# ethernet_camera.net
KiCad netlist of a schematic drawn in EAGLE
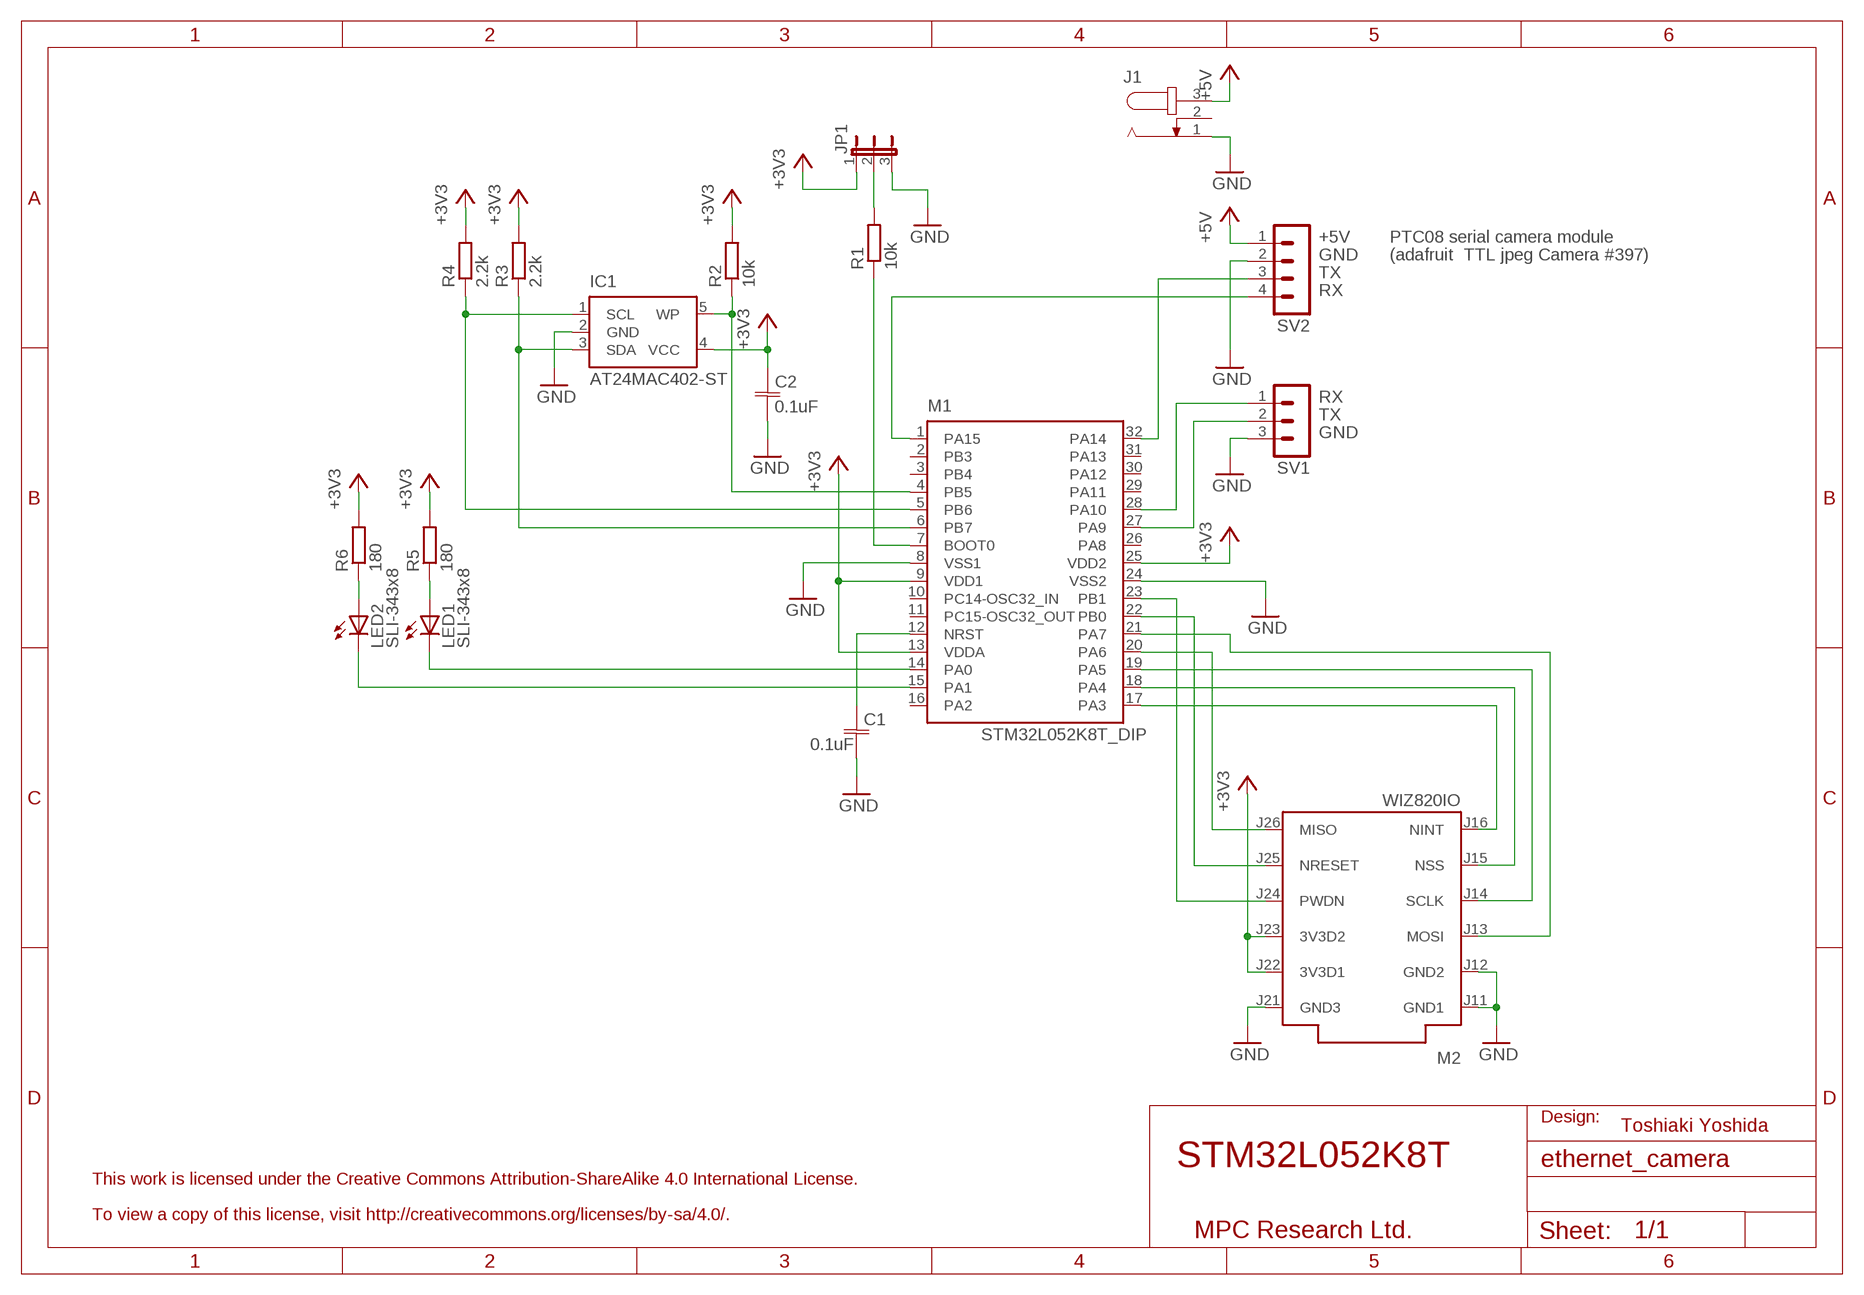
[diagram p0: schematic, sheet 1]

(export (version "E")
  (design (tool "Eeschema 10.0.6"))
  (components
    (comp (ref "C1")
      (value "0.1uF")
      (footprint "eagle-import:C050-024X044")
      (libsource (lib "eagle-import") (part "C-JIS050-024X044"))
    )
    (comp (ref "C2")
      (value "0.1uF")
      (footprint "eagle-import:C050-024X044")
      (libsource (lib "eagle-import") (part "C-JIS050-024X044"))
    )
    (comp (ref "IC1")
      (value "AT24MAC402-ST")
      (footprint "eagle-import:SOT23-5L")
      (libsource (lib "eagle-import") (part "AT24MAC402-ST"))
    )
    (comp (ref "J1")
      (value "JACK-PLUG0")
      (footprint "eagle-import:SPC4077")
      (libsource (lib "eagle-import") (part "JACK-PLUG0"))
    )
    (comp (ref "JP1")
      (value "JP2E")
      (footprint "eagle-import:JP2")
      (libsource (lib "eagle-import") (part "JP2E"))
    )
    (comp (ref "LED1")
      (value "SLI-343x8")
      (footprint "eagle-import:LED3MM")
      (libsource (lib "eagle-import") (part "LED3MM"))
    )
    (comp (ref "LED2")
      (value "SLI-343x8")
      (footprint "eagle-import:LED3MM")
      (libsource (lib "eagle-import") (part "LED3MM"))
    )
    (comp (ref "M1")
      (value "STM32L052K8T_DIP")
      (footprint "eagle-import:DIP32")
      (libsource (lib "eagle-import") (part "STM32L052K8T_DIP"))
    )
    (comp (ref "M2")
      (value "WIZ820IO")
      (footprint "eagle-import:WIZ820IO")
      (libsource (lib "eagle-import") (part "WIZ820IO"))
    )
    (comp (ref "R1")
      (value "10k")
      (footprint "eagle-import:0207_2V")
      (libsource (lib "eagle-import") (part "R-EU_0207/2V"))
    )
    (comp (ref "R2")
      (value "10k")
      (footprint "eagle-import:0207_2V")
      (libsource (lib "eagle-import") (part "R-EU_0207/2V"))
    )
    (comp (ref "R3")
      (value "2.2k")
      (footprint "eagle-import:0207_2V")
      (libsource (lib "eagle-import") (part "R-EU_0207/2V"))
    )
    (comp (ref "R4")
      (value "2.2k")
      (footprint "eagle-import:0207_2V")
      (libsource (lib "eagle-import") (part "R-EU_0207/2V"))
    )
    (comp (ref "R5")
      (value "180")
      (footprint "eagle-import:0207_2V")
      (libsource (lib "eagle-import") (part "R-EU_0207/2V"))
    )
    (comp (ref "R6")
      (value "180")
      (footprint "eagle-import:0207_2V")
      (libsource (lib "eagle-import") (part "R-EU_0207/2V"))
    )
    (comp (ref "SV1")
      (value "MA03-1")
      (footprint "eagle-import:MA03-1")
      (libsource (lib "eagle-import") (part "MA03-1"))
    )
    (comp (ref "SV2")
      (value "MA04-1")
      (footprint "eagle-import:MA04-1")
      (libsource (lib "eagle-import") (part "MA04-1"))
    )
  )
  (nets
    (net (code "1") (name "+3V3") (class "Default")
      (node (ref "C2") (pin "1") (pinfunction "1_1") (pintype "passive"))
      (node (ref "IC1") (pin "4") (pinfunction "VCC_4") (pintype "power_in"))
      (node (ref "JP1") (pin "1") (pinfunction "1_1") (pintype "passive"))
      (node (ref "M1") (pin "13") (pinfunction "VDDA_13") (pintype "power_in"))
      (node (ref "M1") (pin "25") (pinfunction "VDD2_25") (pintype "bidirectional"))
      (node (ref "M1") (pin "9") (pinfunction "VDD1_9") (pintype "power_in"))
      (node (ref "M2") (pin "J22") (pinfunction "3V3D1_J22") (pintype "power_in"))
      (node (ref "M2") (pin "J23") (pinfunction "3V3D2_J23") (pintype "power_in"))
      (node (ref "R2") (pin "2") (pinfunction "2_2") (pintype "passive"))
      (node (ref "R3") (pin "2") (pinfunction "2_2") (pintype "passive"))
      (node (ref "R4") (pin "2") (pinfunction "2_2") (pintype "passive"))
      (node (ref "R5") (pin "2") (pinfunction "2_2") (pintype "passive"))
      (node (ref "R6") (pin "2") (pinfunction "2_2") (pintype "passive"))
    )
    (net (code "2") (name "+5V") (class "Default")
      (node (ref "J1") (pin "3") (pinfunction "3_3") (pintype "passive"))
      (node (ref "SV2") (pin "1") (pinfunction "1_1") (pintype "passive"))
    )
    (net (code "3") (name "GND") (class "Default")
      (node (ref "C1") (pin "2") (pinfunction "2_2") (pintype "passive"))
      (node (ref "C2") (pin "2") (pinfunction "2_2") (pintype "passive"))
      (node (ref "IC1") (pin "2") (pinfunction "GND_2") (pintype "power_in"))
      (node (ref "J1") (pin "1") (pinfunction "1_1") (pintype "passive"))
      (node (ref "JP1") (pin "3") (pinfunction "3_3") (pintype "passive"))
      (node (ref "M1") (pin "24") (pinfunction "VSS2_24") (pintype "power_in"))
      (node (ref "M1") (pin "8") (pinfunction "VSS1_8") (pintype "power_in"))
      (node (ref "M2") (pin "J11") (pinfunction "GND1_J11") (pintype "power_in"))
      (node (ref "M2") (pin "J12") (pinfunction "GND2_J12") (pintype "power_in"))
      (node (ref "M2") (pin "J21") (pinfunction "GND3_J21") (pintype "power_in"))
      (node (ref "SV1") (pin "3") (pinfunction "3_3") (pintype "passive"))
      (node (ref "SV2") (pin "2") (pinfunction "2_2") (pintype "passive"))
    )
    (net (code "4") (name "Net-(IC1-SCL)") (class "Default")
      (node (ref "IC1") (pin "1") (pinfunction "SCL_1") (pintype "input"))
      (node (ref "M1") (pin "5") (pinfunction "PB6_5") (pintype "bidirectional"))
      (node (ref "R4") (pin "1") (pinfunction "1_1") (pintype "passive"))
    )
    (net (code "5") (name "Net-(IC1-SDA)") (class "Default")
      (node (ref "IC1") (pin "3") (pinfunction "SDA_3") (pintype "bidirectional"))
      (node (ref "M1") (pin "6") (pinfunction "PB7_6") (pintype "bidirectional"))
      (node (ref "R3") (pin "1") (pinfunction "1_1") (pintype "passive"))
    )
    (net (code "6") (name "Net-(IC1-WP)") (class "Default")
      (node (ref "IC1") (pin "5") (pinfunction "WP_5") (pintype "input"))
      (node (ref "M1") (pin "4") (pinfunction "PB5_4") (pintype "bidirectional"))
      (node (ref "R2") (pin "1") (pinfunction "1_1") (pintype "passive"))
    )
    (net (code "7") (name "Net-(JP1-Pad2)") (class "Default")
      (node (ref "JP1") (pin "2") (pinfunction "2_2") (pintype "passive"))
      (node (ref "R1") (pin "2") (pinfunction "2_2") (pintype "passive"))
    )
    (net (code "8") (name "Net-(LED1-C)") (class "Default")
      (node (ref "LED1") (pin "K") (pinfunction "C_K") (pintype "passive"))
      (node (ref "M1") (pin "14") (pinfunction "PA0_14") (pintype "bidirectional"))
    )
    (net (code "9") (name "Net-(LED1-PadA)") (class "Default")
      (node (ref "LED1") (pin "A") (pinfunction "A_A") (pintype "passive"))
      (node (ref "R5") (pin "1") (pinfunction "1_1") (pintype "passive"))
    )
    (net (code "10") (name "Net-(LED2-C)") (class "Default")
      (node (ref "LED2") (pin "K") (pinfunction "C_K") (pintype "passive"))
      (node (ref "M1") (pin "15") (pinfunction "PA1_15") (pintype "bidirectional"))
    )
    (net (code "11") (name "Net-(LED2-PadA)") (class "Default")
      (node (ref "LED2") (pin "A") (pinfunction "A_A") (pintype "passive"))
      (node (ref "R6") (pin "1") (pinfunction "1_1") (pintype "passive"))
    )
    (net (code "12") (name "Net-(M1-BOOT0)") (class "Default")
      (node (ref "M1") (pin "7") (pinfunction "BOOT0_7") (pintype "bidirectional"))
      (node (ref "R1") (pin "1") (pinfunction "1_1") (pintype "passive"))
    )
    (net (code "13") (name "Net-(M1-NRST)") (class "Default")
      (node (ref "C1") (pin "1") (pinfunction "1_1") (pintype "passive"))
      (node (ref "M1") (pin "12") (pinfunction "NRST_12") (pintype "bidirectional"))
    )
    (net (code "14") (name "Net-(M1-PA3)") (class "Default")
      (node (ref "M1") (pin "17") (pinfunction "PA3_17") (pintype "bidirectional"))
      (node (ref "M2") (pin "J16") (pinfunction "NINT_J16") (pintype "output"))
    )
    (net (code "15") (name "Net-(M1-PA4)") (class "Default")
      (node (ref "M1") (pin "18") (pinfunction "PA4_18") (pintype "bidirectional"))
      (node (ref "M2") (pin "J15") (pinfunction "NSS_J15") (pintype "input"))
    )
    (net (code "16") (name "Net-(M1-PA5)") (class "Default")
      (node (ref "M1") (pin "19") (pinfunction "PA5_19") (pintype "bidirectional"))
      (node (ref "M2") (pin "J14") (pinfunction "SCLK_J14") (pintype "input"))
    )
    (net (code "17") (name "Net-(M1-PA6)") (class "Default")
      (node (ref "M1") (pin "20") (pinfunction "PA6_20") (pintype "bidirectional"))
      (node (ref "M2") (pin "J26") (pinfunction "MISO_J26") (pintype "tri_state"))
    )
    (net (code "18") (name "Net-(M1-PA7)") (class "Default")
      (node (ref "M1") (pin "21") (pinfunction "PA7_21") (pintype "bidirectional"))
      (node (ref "M2") (pin "J13") (pinfunction "MOSI_J13") (pintype "input"))
    )
    (net (code "19") (name "Net-(M1-PA9)") (class "Default")
      (node (ref "M1") (pin "27") (pinfunction "PA9_27") (pintype "bidirectional"))
      (node (ref "SV1") (pin "2") (pinfunction "2_2") (pintype "passive"))
    )
    (net (code "20") (name "Net-(M1-PA10)") (class "Default")
      (node (ref "M1") (pin "28") (pinfunction "PA10_28") (pintype "bidirectional"))
      (node (ref "SV1") (pin "1") (pinfunction "1_1") (pintype "passive"))
    )
    (net (code "21") (name "Net-(M1-PA14)") (class "Default")
      (node (ref "M1") (pin "32") (pinfunction "PA14_32") (pintype "bidirectional"))
      (node (ref "SV2") (pin "3") (pinfunction "3_3") (pintype "passive"))
    )
    (net (code "22") (name "Net-(M1-PA15)") (class "Default")
      (node (ref "M1") (pin "1") (pinfunction "PA15_1") (pintype "bidirectional"))
      (node (ref "SV2") (pin "4") (pinfunction "4_4") (pintype "passive"))
    )
    (net (code "23") (name "Net-(M1-PB0)") (class "Default")
      (node (ref "M1") (pin "22") (pinfunction "PB0_22") (pintype "bidirectional"))
      (node (ref "M2") (pin "J25") (pinfunction "NRESET_J25") (pintype "input"))
    )
    (net (code "24") (name "Net-(M1-PB1)") (class "Default")
      (node (ref "M1") (pin "23") (pinfunction "PB1_23") (pintype "bidirectional"))
      (node (ref "M2") (pin "J24") (pinfunction "PWDN_J24") (pintype "input"))
    )
    (net (code "25") (name "unconnected-(J1-Pad2)") (class "Default")
      (node (ref "J1") (pin "2") (pinfunction "2_2") (pintype "passive"))
    )
    (net (code "26") (name "unconnected-(M1-PA2-Pad16)") (class "Default")
      (node (ref "M1") (pin "16") (pinfunction "PA2_16") (pintype "bidirectional"))
    )
    (net (code "27") (name "unconnected-(M1-PA8-Pad26)") (class "Default")
      (node (ref "M1") (pin "26") (pinfunction "PA8_26") (pintype "bidirectional"))
    )
    (net (code "28") (name "unconnected-(M1-PA11-Pad29)") (class "Default")
      (node (ref "M1") (pin "29") (pinfunction "PA11_29") (pintype "bidirectional"))
    )
    (net (code "29") (name "unconnected-(M1-PA12-Pad30)") (class "Default")
      (node (ref "M1") (pin "30") (pinfunction "PA12_30") (pintype "bidirectional"))
    )
    (net (code "30") (name "unconnected-(M1-PA13-Pad31)") (class "Default")
      (node (ref "M1") (pin "31") (pinfunction "PA13_31") (pintype "bidirectional"))
    )
    (net (code "31") (name "unconnected-(M1-PB3-Pad2)") (class "Default")
      (node (ref "M1") (pin "2") (pinfunction "PB3_2") (pintype "bidirectional"))
    )
    (net (code "32") (name "unconnected-(M1-PB4-Pad3)") (class "Default")
      (node (ref "M1") (pin "3") (pinfunction "PB4_3") (pintype "bidirectional"))
    )
    (net (code "33") (name "unconnected-(M1-PC14-OSC32_IN-Pad10)") (class "Default")
      (node (ref "M1") (pin "10") (pinfunction "PC14-OSC32_IN_10") (pintype "bidirectional"))
    )
    (net (code "34") (name "unconnected-(M1-PC15-OSC32_OUT-Pad11)") (class "Default")
      (node (ref "M1") (pin "11") (pinfunction "PC15-OSC32_OUT_11") (pintype "bidirectional"))
    )
  )
)
